# principle_diagram_boost_converter.net
KiCad netlist of a schematic drawn in Altium Designer
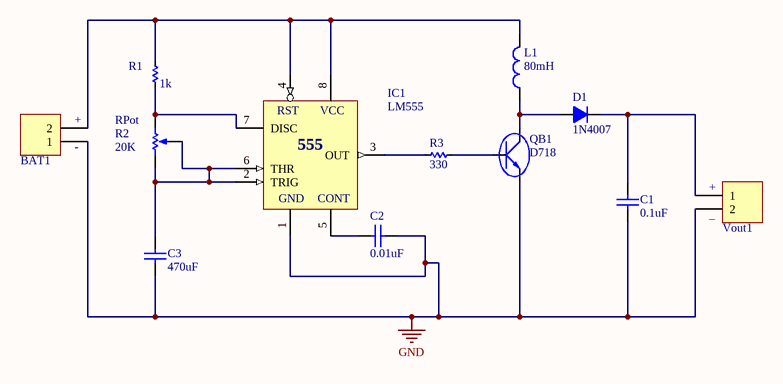
[diagram p0: principle_diagram_boost_converter.SchDoc]

(export (version "E")
  (design (tool "Eeschema 10.0.6"))
  (components
    (comp (ref "BAT1")
      (value "Header 2_1")
      (footprint "HED2")
      (description "Header, 2-Pin")
      (fields (field (name "MANUFACTURER") "Generic Components"))
      (libsource (lib "syhaunguyen") (part "Header 2_1"))
    )
    (comp (ref "C1")
      (value "0.1uF")
      (footprint "Cap Non-Pol 3mm")
      (description "Non-polarized Capacitor")
      (fields (field (name "Comment") "Cap Non-pol") (field (name "PUBLISHER") "Altium Limited"))
      (libsource (lib "hphonglib") (part "Cap Non-pol"))
    )
    (comp (ref "C2")
      (value "0.01uF")
      (footprint "Cap Non-Pol 3mm")
      (description "Non-polarized Capacitor")
      (fields (field (name "Comment") "Cap Non-pol") (field (name "PUBLISHER") "Altium Limited"))
      (libsource (lib "hphonglib") (part "Cap Non-pol"))
    )
    (comp (ref "C3")
      (value "470uF")
      (footprint "Cap Non-Pol 3mm")
      (description "Non-polarized Capacitor")
      (fields (field (name "Comment") "Cap Non-pol") (field (name "PUBLISHER") "Altium Limited"))
      (libsource (lib "hphonglib") (part "Cap Non-pol"))
    )
    (comp (ref "D1")
      (value "1N4007")
      (footprint "D2A")
      (description "Diode 1A")
      (libsource (lib "hphonglib") (part "D1A"))
    )
    (comp (ref "IC1")
      (value "LM555")
      (footprint "DIP8")
      (description "Timer")
      (libsource (lib "TechMT.VN_Lib_Project v2") (part "LM555"))
    )
    (comp (ref "L1")
      (value "80mH")
      (footprint "L/0.4")
      (description "Inductor")
      (libsource (lib "hphonglib") (part "L1"))
    )
    (comp (ref "QB1")
      (value "D718")
      (footprint "QTO-247")
      (description "Transistor Power Supply")
      (libsource (lib "hphonglib") (part "D718_1"))
    )
    (comp (ref "R1")
      (value "1k")
      (footprint "RES-1/4W")
      (description "Res")
      (fields
        (field (name "MANUFACTURER") "Generic Components")
        (field (name "PUBLISHER") "Altium Hobart Technology Centre")
      )
      (libsource (lib "TechMT.VN_Lib_Project v2") (part "Res"))
    )
    (comp (ref "R2")
      (value "RPot")
      (footprint "VR5")
      (description "Potentiometer")
      (fields (field (name "ALTIUM_VALUE") "20K") (field (name "PUBLISHER") "Altium Limited"))
      (libsource (lib "Miscellaneous Devices") (part "RPot"))
    )
    (comp (ref "R3")
      (value "330")
      (footprint "RES-1/4W")
      (description "Res")
      (fields
        (field (name "MANUFACTURER") "Generic Components")
        (field (name "PUBLISHER") "Altium Hobart Technology Centre")
      )
      (libsource (lib "TechMT.VN_Lib_Project v2") (part "Res"))
    )
    (comp (ref "Vout1")
      (value "Header 2_1")
      (footprint "HED2")
      (description "Header, 2-Pin")
      (fields (field (name "MANUFACTURER") "Generic Components"))
      (libsource (lib "") (part "Header 2_1_1"))
    )
  )
  (nets
    (net (code "1") (name "GND") (class "Default")
      (node (ref "BAT1") (pin "1") (pinfunction "1_1") (pintype "passive"))
      (node (ref "C1") (pin "1") (pinfunction "1_1") (pintype "passive"))
      (node (ref "C2") (pin "1") (pinfunction "1_1") (pintype "passive"))
      (node (ref "C3") (pin "1") (pinfunction "1_1") (pintype "passive"))
      (node (ref "IC1") (pin "1") (pinfunction "GND_1") (pintype "power_in"))
      (node (ref "QB1") (pin "3") (pinfunction "E_3") (pintype "passive"))
      (node (ref "Vout1") (pin "2") (pinfunction "2_2") (pintype "passive"))
    )
    (net (code "2") (name "Net-(D1-A)") (class "Default")
      (node (ref "D1") (pin "1") (pinfunction "A_1") (pintype "passive"))
      (node (ref "L1") (pin "1") (pinfunction "1_1") (pintype "passive"))
      (node (ref "QB1") (pin "2") (pinfunction "C_2") (pintype "passive"))
    )
    (net (code "3") (name "Net-(D1-K)") (class "Default")
      (node (ref "C1") (pin "2") (pinfunction "2_2") (pintype "passive"))
      (node (ref "D1") (pin "2") (pinfunction "K_2") (pintype "passive"))
      (node (ref "Vout1") (pin "1") (pinfunction "1_1") (pintype "passive"))
    )
    (net (code "4") (name "Net-(IC1-CONT)") (class "Default")
      (node (ref "C2") (pin "2") (pinfunction "2_2") (pintype "passive"))
      (node (ref "IC1") (pin "5") (pinfunction "CONT_5") (pintype "passive"))
    )
    (net (code "5") (name "Net-(IC1-DISC)") (class "Default")
      (node (ref "IC1") (pin "7") (pinfunction "DISC_7") (pintype "open_collector"))
      (node (ref "R1") (pin "1") (pinfunction "1_1") (pintype "passive"))
      (node (ref "R2") (pin "2") (pinfunction "BOT_2") (pintype "passive"))
    )
    (net (code "6") (name "Net-(IC1-OUT)") (class "Default")
      (node (ref "IC1") (pin "3") (pinfunction "OUT_3") (pintype "output"))
      (node (ref "R3") (pin "2") (pinfunction "2_2") (pintype "passive"))
    )
    (net (code "7") (name "Net-(IC1-RST)") (class "Default")
      (node (ref "BAT1") (pin "2") (pinfunction "2_2") (pintype "passive"))
      (node (ref "IC1") (pin "4") (pinfunction "RST_4") (pintype "input"))
      (node (ref "IC1") (pin "8") (pinfunction "VCC_8") (pintype "power_in"))
      (node (ref "L1") (pin "2") (pinfunction "2_2") (pintype "passive"))
      (node (ref "R1") (pin "2") (pinfunction "2_2") (pintype "passive"))
    )
    (net (code "8") (name "Net-(IC1-THR)") (class "Default")
      (node (ref "C3") (pin "2") (pinfunction "2_2") (pintype "passive"))
      (node (ref "IC1") (pin "2") (pinfunction "TRIG_2") (pintype "input"))
      (node (ref "IC1") (pin "6") (pinfunction "THR_6") (pintype "input"))
      (node (ref "R2") (pin "1") (pinfunction "TOP_1") (pintype "passive"))
      (node (ref "R2") (pin "3") (pinfunction "TAP_3") (pintype "passive"))
    )
    (net (code "9") (name "Net-(QB1-B)") (class "Default")
      (node (ref "QB1") (pin "1") (pinfunction "B_1") (pintype "passive"))
      (node (ref "R3") (pin "1") (pinfunction "1_1") (pintype "passive"))
    )
  )
)
